# CH572D-DG-R0.net
KiCad netlist of a schematic drawn in Altium Designer
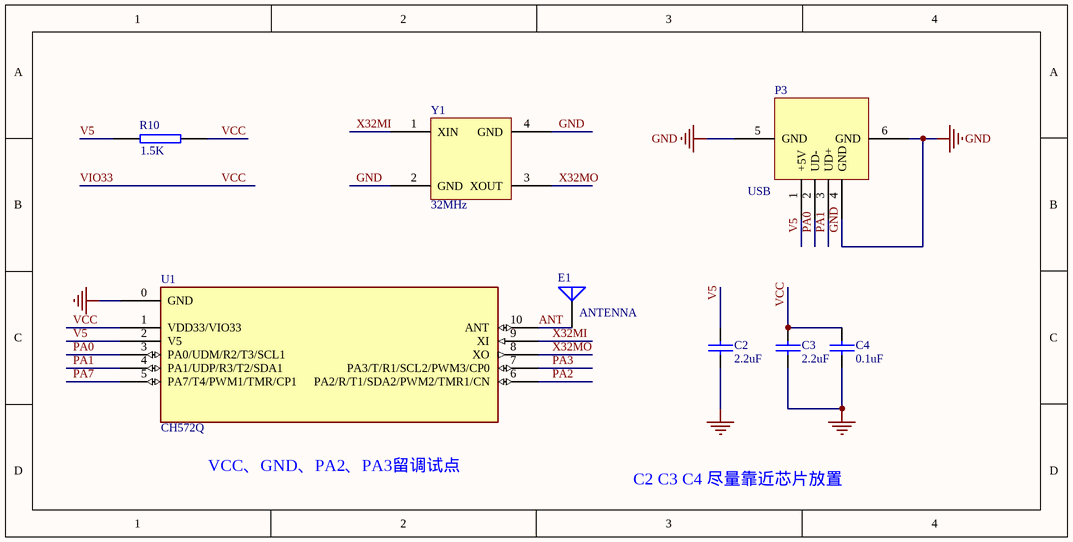
[diagram p0: CH572D-DG-R0.SchDoc]

(export (version "E")
  (design (tool "Eeschema 10.0.6"))
  (components
    (comp (ref "C2")
      (value "2.2uF")
      (footprint "0402_C")
      (description "Capacitor")
      (libsource (lib "*") (part "CAP"))
    )
    (comp (ref "C3")
      (value "2.2uF")
      (footprint "0402_C")
      (description "Capacitor")
      (libsource (lib "*") (part "CAP"))
    )
    (comp (ref "C4")
      (value "0.1uF")
      (footprint "0402_C")
      (description "Capacitor")
      (libsource (lib "*") (part "CAP"))
    )
    (comp (ref "E1")
      (value "ANTENNA")
      (footprint "ANT-F-1-2.4G-0.8mmFR4")
      (description "Generic Antenna")
      (libsource (lib "*") (part "ANTENNA"))
    )
    (comp (ref "P3") (value "USB") (footprint "USBAM-4P") (libsource (lib "Schlib1") (part "USB")))
    (comp (ref "R10") (value "1.5K") (footprint "0402") (libsource (lib "*") (part "RES2")))
    (comp (ref "U1")
      (value "CH572Q")
      (footprint "DFN10_3X3")
      (description "RISC-V MCU with BLE/2.4GHz Wireless/USB/UART/I2C/PWM/CMP")
      (libsource (lib "DHXXXSCHd") (part "CH572Q"))
    )
    (comp (ref "Y1") (value "32MHz") (footprint "XT2016") (libsource (lib "wch_sch_others") (part "晶体")))
  )
  (nets
    (net (code "1") (name "/ANT") (class "Default")
      (node (ref "E1") (pin "1") (pinfunction "A_1") (pintype "passive"))
      (node (ref "U1") (pin "10") (pinfunction "ANT_10") (pintype "bidirectional"))
    )
    (net (code "2") (name "/PA0") (class "Default")
      (node (ref "P3") (pin "2") (pinfunction "UD-_2") (pintype "passive"))
      (node (ref "U1") (pin "3") (pinfunction "PA0/UDM/R2/T3/SCL1_3") (pintype "bidirectional"))
    )
    (net (code "3") (name "/PA1") (class "Default")
      (node (ref "P3") (pin "3") (pinfunction "UD+_3") (pintype "passive"))
      (node (ref "U1") (pin "4") (pinfunction "PA1/UDP/R3/T2/SDA1_4") (pintype "bidirectional"))
    )
    (net (code "4") (name "/PA2") (class "Default")
      (node (ref "U1") (pin "6") (pinfunction "PA2/R/T1/SDA2/PWM2/TMR1/CN_6") (pintype "bidirectional"))
    )
    (net (code "5") (name "/PA3") (class "Default")
      (node (ref "U1") (pin "7") (pinfunction "PA3/T/R1/SCL2/PWM3/CP0_7") (pintype "bidirectional"))
    )
    (net (code "6") (name "/PA7") (class "Default")
      (node (ref "U1") (pin "5") (pinfunction "PA7/T4/PWM1/TMR/CP1_5") (pintype "bidirectional"))
    )
    (net (code "7") (name "/V5") (class "Default")
      (node (ref "C2") (pin "1") (pinfunction "1_1") (pintype "passive"))
      (node (ref "P3") (pin "1") (pinfunction "+5V_1") (pintype "passive"))
      (node (ref "R10") (pin "1") (pinfunction "1_1") (pintype "passive"))
      (node (ref "U1") (pin "2") (pinfunction "V5_2") (pintype "power_in"))
    )
    (net (code "8") (name "/VCC") (class "Default")
      (node (ref "C3") (pin "1") (pinfunction "1_1") (pintype "passive"))
      (node (ref "C4") (pin "1") (pinfunction "1_1") (pintype "passive"))
      (node (ref "R10") (pin "2") (pinfunction "2_2") (pintype "passive"))
      (node (ref "U1") (pin "1") (pinfunction "VDD33/VIO33_1") (pintype "power_in"))
    )
    (net (code "9") (name "/X32MI") (class "Default")
      (node (ref "U1") (pin "9") (pinfunction "XI_9") (pintype "input"))
      (node (ref "Y1") (pin "1") (pinfunction "XIN_1") (pintype "passive"))
    )
    (net (code "10") (name "/X32MO") (class "Default")
      (node (ref "U1") (pin "8") (pinfunction "XO_8") (pintype "output"))
      (node (ref "Y1") (pin "3") (pinfunction "XOUT_3") (pintype "passive"))
    )
    (net (code "11") (name "GND") (class "Default")
      (node (ref "C2") (pin "2") (pinfunction "2_2") (pintype "passive"))
      (node (ref "C3") (pin "2") (pinfunction "2_2") (pintype "passive"))
      (node (ref "C4") (pin "2") (pinfunction "2_2") (pintype "passive"))
      (node (ref "P3") (pin "4") (pinfunction "GND_4") (pintype "passive"))
      (node (ref "P3") (pin "5") (pinfunction "GND_5") (pintype "passive"))
      (node (ref "P3") (pin "6") (pinfunction "GND_6") (pintype "passive"))
      (node (ref "U1") (pin "0") (pinfunction "GND_0") (pintype "power_in"))
      (node (ref "Y1") (pin "2") (pinfunction "GND_2") (pintype "passive"))
      (node (ref "Y1") (pin "4") (pinfunction "GND_4") (pintype "passive"))
    )
  )
)
